# STM32F103RCT6.net
KiCad netlist of a schematic drawn in EasyEDA Pro
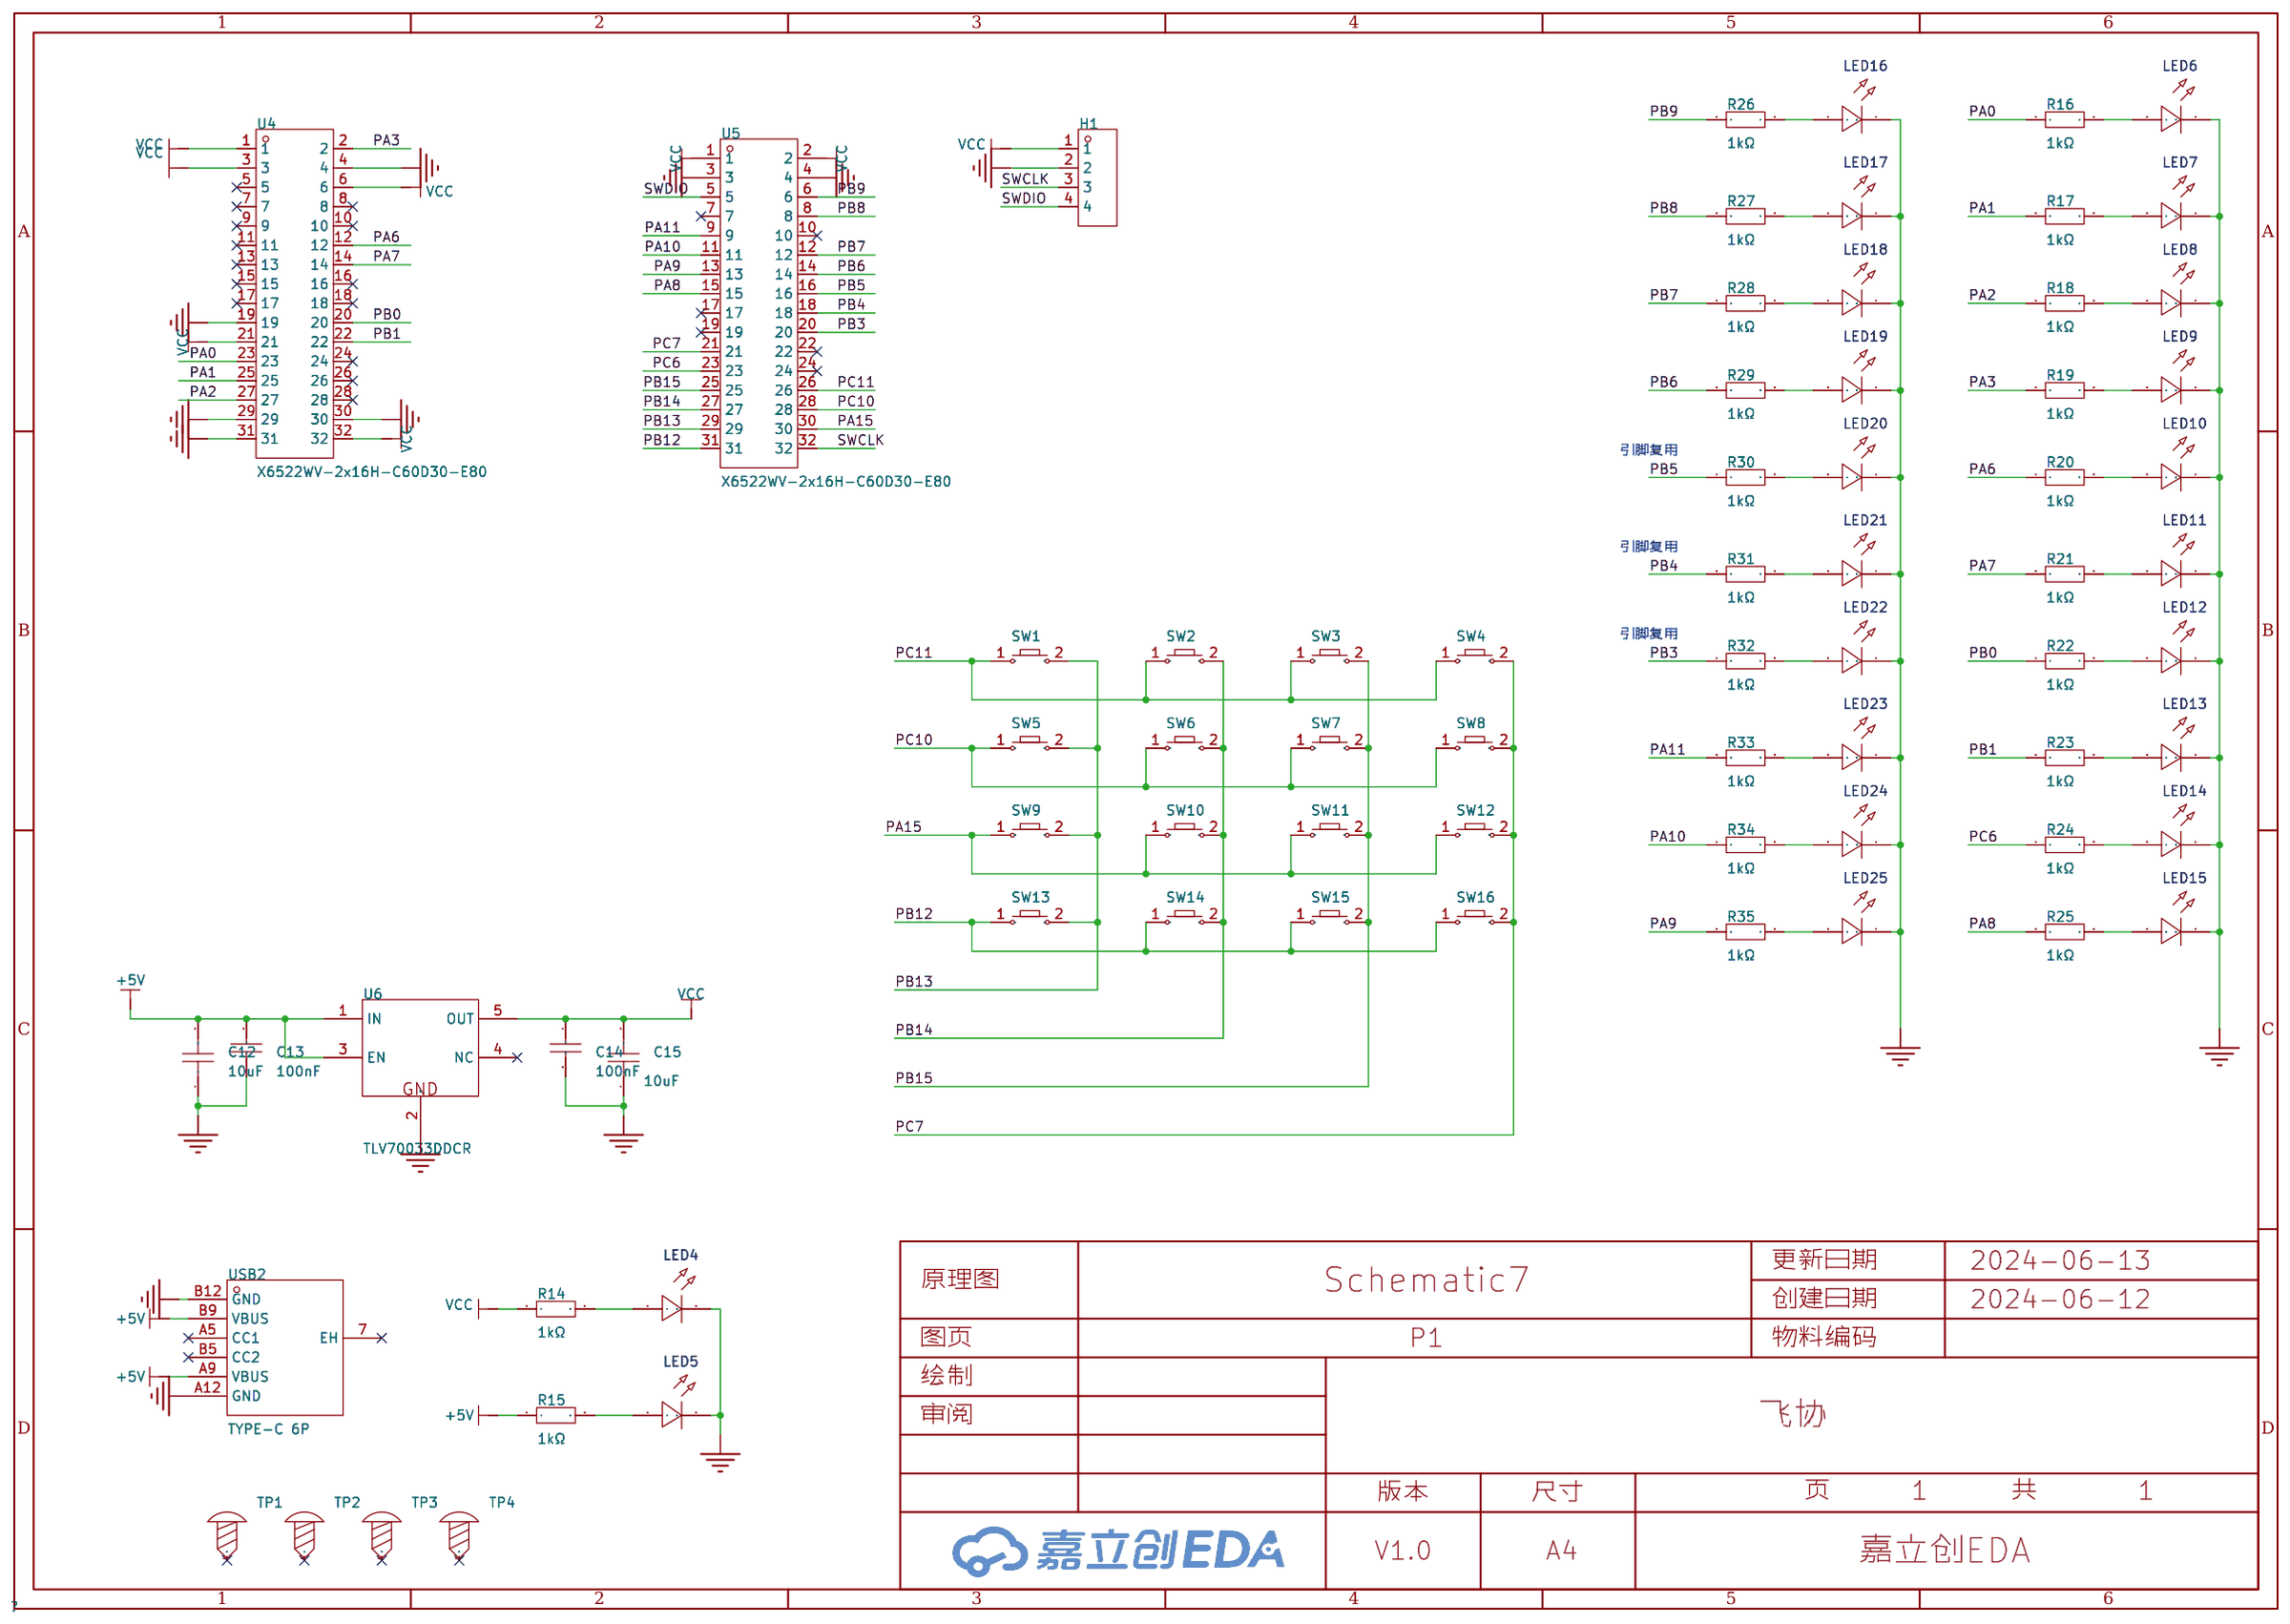
[diagram p0: schematic sheet]

(export (version "E")
  (design (tool "Eeschema 10.0.6"))
  (components
    (comp (ref "C12")
      (value "10uF")
      (fields
        (field (name "Manufacturer Part") "CL21A106KAYNNNE")
        (field (name "Manufacturer") "SAMSUNG(三星)")
      )
      (libsource (lib "easyedapro") (part "CL21A106KAYNNNE"))
    )
    (comp (ref "C13")
      (value "100nF")
      (footprint "easyedapro:C0805")
      (description "容值:100nF;精度:±10%;额定电压:50V;材质(温度系数):X7R;")
      (fields (field (name "Manufacturer Part") "0805B104K500NT") (field (name "Manufacturer") "FH(风华)"))
      (libsource (lib "easyedapro") (part "0805B104K500NT"))
    )
    (comp (ref "C14")
      (value "100nF")
      (footprint "easyedapro:C0805")
      (description "容值:100nF;精度:±10%;额定电压:50V;材质(温度系数):X7R;")
      (fields (field (name "Manufacturer Part") "0805B104K500NT") (field (name "Manufacturer") "FH(风华)"))
      (libsource (lib "easyedapro") (part "0805B104K500NT"))
    )
    (comp (ref "C15")
      (value "10uF")
      (fields
        (field (name "Manufacturer Part") "CL21A106KAYNNNE")
        (field (name "Manufacturer") "SAMSUNG(三星)")
      )
      (libsource (lib "easyedapro") (part "CL21A106KAYNNNE"))
    )
    (comp (ref "H1")
      (value "~")
      (footprint "easyedapro:HDR-TH_4P-P2.54-V-F")
      (libsource (lib "easyedapro") (part "2.54-1*4P母"))
    )
    (comp (ref "LED4")
      (value "~")
      (footprint "easyedapro:LED_0805")
      (libsource (lib "easyedapro") (part "LED_B"))
    )
    (comp (ref "LED5")
      (value "~")
      (footprint "easyedapro:LED_0805")
      (libsource (lib "easyedapro") (part "LED_B"))
    )
    (comp (ref "LED6")
      (value "~")
      (footprint "easyedapro:LED_0805")
      (libsource (lib "easyedapro") (part "LED_B"))
    )
    (comp (ref "LED7")
      (value "~")
      (footprint "easyedapro:LED_0805")
      (libsource (lib "easyedapro") (part "LED_B"))
    )
    (comp (ref "LED8")
      (value "~")
      (footprint "easyedapro:LED_0805")
      (libsource (lib "easyedapro") (part "LED_B"))
    )
    (comp (ref "LED9")
      (value "~")
      (footprint "easyedapro:LED_0805")
      (libsource (lib "easyedapro") (part "LED_B"))
    )
    (comp (ref "LED10")
      (value "~")
      (footprint "easyedapro:LED_0805")
      (libsource (lib "easyedapro") (part "LED_B"))
    )
    (comp (ref "LED11")
      (value "~")
      (footprint "easyedapro:LED_0805")
      (libsource (lib "easyedapro") (part "LED_B"))
    )
    (comp (ref "LED12")
      (value "~")
      (footprint "easyedapro:LED_0805")
      (libsource (lib "easyedapro") (part "LED_B"))
    )
    (comp (ref "LED13")
      (value "~")
      (footprint "easyedapro:LED_0805")
      (libsource (lib "easyedapro") (part "LED_B"))
    )
    (comp (ref "LED14")
      (value "~")
      (footprint "easyedapro:LED_0805")
      (libsource (lib "easyedapro") (part "LED_B"))
    )
    (comp (ref "LED15")
      (value "~")
      (footprint "easyedapro:LED_0805")
      (libsource (lib "easyedapro") (part "LED_B"))
    )
    (comp (ref "LED16")
      (value "~")
      (footprint "easyedapro:LED_0805")
      (libsource (lib "easyedapro") (part "LED_B"))
    )
    (comp (ref "LED17")
      (value "~")
      (footprint "easyedapro:LED_0805")
      (libsource (lib "easyedapro") (part "LED_B"))
    )
    (comp (ref "LED18")
      (value "~")
      (footprint "easyedapro:LED_0805")
      (libsource (lib "easyedapro") (part "LED_B"))
    )
    (comp (ref "LED19")
      (value "~")
      (footprint "easyedapro:LED_0805")
      (libsource (lib "easyedapro") (part "LED_B"))
    )
    (comp (ref "LED20")
      (value "~")
      (footprint "easyedapro:LED_0805")
      (libsource (lib "easyedapro") (part "LED_B"))
    )
    (comp (ref "LED21")
      (value "~")
      (footprint "easyedapro:LED_0805")
      (libsource (lib "easyedapro") (part "LED_B"))
    )
    (comp (ref "LED22")
      (value "~")
      (footprint "easyedapro:LED_0805")
      (libsource (lib "easyedapro") (part "LED_B"))
    )
    (comp (ref "LED23")
      (value "~")
      (footprint "easyedapro:LED_0805")
      (libsource (lib "easyedapro") (part "LED_B"))
    )
    (comp (ref "LED24")
      (value "~")
      (footprint "easyedapro:LED_0805")
      (libsource (lib "easyedapro") (part "LED_B"))
    )
    (comp (ref "LED25")
      (value "~")
      (footprint "easyedapro:LED_0805")
      (libsource (lib "easyedapro") (part "LED_B"))
    )
    (comp (ref "R14")
      (value "1kΩ")
      (footprint "easyedapro:R0805")
      (description "电阻类型:厚膜电阻;阻值:1kΩ;精度:±1%;功率:125mW;最大工作电压:150V;温度系数:±100ppm/°C;")
      (fields
        (field (name "Manufacturer Part") "0805W8F1001T5E")
        (field (name "Manufacturer") "UNI-ROYAL(厚声)")
      )
      (libsource (lib "easyedapro") (part "0805W8F1001T5E"))
    )
    (comp (ref "R15")
      (value "1kΩ")
      (footprint "easyedapro:R0805")
      (description "电阻类型:厚膜电阻;阻值:1kΩ;精度:±1%;功率:125mW;最大工作电压:150V;温度系数:±100ppm/°C;")
      (fields
        (field (name "Manufacturer Part") "0805W8F1001T5E")
        (field (name "Manufacturer") "UNI-ROYAL(厚声)")
      )
      (libsource (lib "easyedapro") (part "0805W8F1001T5E"))
    )
    (comp (ref "R16")
      (value "1kΩ")
      (footprint "easyedapro:R0805")
      (description "电阻类型:厚膜电阻;阻值:1kΩ;精度:±1%;功率:125mW;最大工作电压:150V;温度系数:±100ppm/°C;")
      (fields
        (field (name "Manufacturer Part") "0805W8F1001T5E")
        (field (name "Manufacturer") "UNI-ROYAL(厚声)")
      )
      (libsource (lib "easyedapro") (part "0805W8F1001T5E"))
    )
    (comp (ref "R17")
      (value "1kΩ")
      (footprint "easyedapro:R0805")
      (description "电阻类型:厚膜电阻;阻值:1kΩ;精度:±1%;功率:125mW;最大工作电压:150V;温度系数:±100ppm/°C;")
      (fields
        (field (name "Manufacturer Part") "0805W8F1001T5E")
        (field (name "Manufacturer") "UNI-ROYAL(厚声)")
      )
      (libsource (lib "easyedapro") (part "0805W8F1001T5E"))
    )
    (comp (ref "R18")
      (value "1kΩ")
      (footprint "easyedapro:R0805")
      (description "电阻类型:厚膜电阻;阻值:1kΩ;精度:±1%;功率:125mW;最大工作电压:150V;温度系数:±100ppm/°C;")
      (fields
        (field (name "Manufacturer Part") "0805W8F1001T5E")
        (field (name "Manufacturer") "UNI-ROYAL(厚声)")
      )
      (libsource (lib "easyedapro") (part "0805W8F1001T5E"))
    )
    (comp (ref "R19")
      (value "1kΩ")
      (footprint "easyedapro:R0805")
      (description "电阻类型:厚膜电阻;阻值:1kΩ;精度:±1%;功率:125mW;最大工作电压:150V;温度系数:±100ppm/°C;")
      (fields
        (field (name "Manufacturer Part") "0805W8F1001T5E")
        (field (name "Manufacturer") "UNI-ROYAL(厚声)")
      )
      (libsource (lib "easyedapro") (part "0805W8F1001T5E"))
    )
    (comp (ref "R20")
      (value "1kΩ")
      (footprint "easyedapro:R0805")
      (description "电阻类型:厚膜电阻;阻值:1kΩ;精度:±1%;功率:125mW;最大工作电压:150V;温度系数:±100ppm/°C;")
      (fields
        (field (name "Manufacturer Part") "0805W8F1001T5E")
        (field (name "Manufacturer") "UNI-ROYAL(厚声)")
      )
      (libsource (lib "easyedapro") (part "0805W8F1001T5E"))
    )
    (comp (ref "R21")
      (value "1kΩ")
      (footprint "easyedapro:R0805")
      (description "电阻类型:厚膜电阻;阻值:1kΩ;精度:±1%;功率:125mW;最大工作电压:150V;温度系数:±100ppm/°C;")
      (fields
        (field (name "Manufacturer Part") "0805W8F1001T5E")
        (field (name "Manufacturer") "UNI-ROYAL(厚声)")
      )
      (libsource (lib "easyedapro") (part "0805W8F1001T5E"))
    )
    (comp (ref "R22")
      (value "1kΩ")
      (footprint "easyedapro:R0805")
      (description "电阻类型:厚膜电阻;阻值:1kΩ;精度:±1%;功率:125mW;最大工作电压:150V;温度系数:±100ppm/°C;")
      (fields
        (field (name "Manufacturer Part") "0805W8F1001T5E")
        (field (name "Manufacturer") "UNI-ROYAL(厚声)")
      )
      (libsource (lib "easyedapro") (part "0805W8F1001T5E"))
    )
    (comp (ref "R23")
      (value "1kΩ")
      (footprint "easyedapro:R0805")
      (description "电阻类型:厚膜电阻;阻值:1kΩ;精度:±1%;功率:125mW;最大工作电压:150V;温度系数:±100ppm/°C;")
      (fields
        (field (name "Manufacturer Part") "0805W8F1001T5E")
        (field (name "Manufacturer") "UNI-ROYAL(厚声)")
      )
      (libsource (lib "easyedapro") (part "0805W8F1001T5E"))
    )
    (comp (ref "R24")
      (value "1kΩ")
      (footprint "easyedapro:R0805")
      (description "电阻类型:厚膜电阻;阻值:1kΩ;精度:±1%;功率:125mW;最大工作电压:150V;温度系数:±100ppm/°C;")
      (fields
        (field (name "Manufacturer Part") "0805W8F1001T5E")
        (field (name "Manufacturer") "UNI-ROYAL(厚声)")
      )
      (libsource (lib "easyedapro") (part "0805W8F1001T5E"))
    )
    (comp (ref "R25")
      (value "1kΩ")
      (footprint "easyedapro:R0805")
      (description "电阻类型:厚膜电阻;阻值:1kΩ;精度:±1%;功率:125mW;最大工作电压:150V;温度系数:±100ppm/°C;")
      (fields
        (field (name "Manufacturer Part") "0805W8F1001T5E")
        (field (name "Manufacturer") "UNI-ROYAL(厚声)")
      )
      (libsource (lib "easyedapro") (part "0805W8F1001T5E"))
    )
    (comp (ref "R26")
      (value "1kΩ")
      (footprint "easyedapro:R0805")
      (description "电阻类型:厚膜电阻;阻值:1kΩ;精度:±1%;功率:125mW;最大工作电压:150V;温度系数:±100ppm/°C;")
      (fields
        (field (name "Manufacturer Part") "0805W8F1001T5E")
        (field (name "Manufacturer") "UNI-ROYAL(厚声)")
      )
      (libsource (lib "easyedapro") (part "0805W8F1001T5E"))
    )
    (comp (ref "R27")
      (value "1kΩ")
      (footprint "easyedapro:R0805")
      (description "电阻类型:厚膜电阻;阻值:1kΩ;精度:±1%;功率:125mW;最大工作电压:150V;温度系数:±100ppm/°C;")
      (fields
        (field (name "Manufacturer Part") "0805W8F1001T5E")
        (field (name "Manufacturer") "UNI-ROYAL(厚声)")
      )
      (libsource (lib "easyedapro") (part "0805W8F1001T5E"))
    )
    (comp (ref "R28")
      (value "1kΩ")
      (footprint "easyedapro:R0805")
      (description "电阻类型:厚膜电阻;阻值:1kΩ;精度:±1%;功率:125mW;最大工作电压:150V;温度系数:±100ppm/°C;")
      (fields
        (field (name "Manufacturer Part") "0805W8F1001T5E")
        (field (name "Manufacturer") "UNI-ROYAL(厚声)")
      )
      (libsource (lib "easyedapro") (part "0805W8F1001T5E"))
    )
    (comp (ref "R29")
      (value "1kΩ")
      (footprint "easyedapro:R0805")
      (description "电阻类型:厚膜电阻;阻值:1kΩ;精度:±1%;功率:125mW;最大工作电压:150V;温度系数:±100ppm/°C;")
      (fields
        (field (name "Manufacturer Part") "0805W8F1001T5E")
        (field (name "Manufacturer") "UNI-ROYAL(厚声)")
      )
      (libsource (lib "easyedapro") (part "0805W8F1001T5E"))
    )
    (comp (ref "R30")
      (value "1kΩ")
      (footprint "easyedapro:R0805")
      (description "电阻类型:厚膜电阻;阻值:1kΩ;精度:±1%;功率:125mW;最大工作电压:150V;温度系数:±100ppm/°C;")
      (fields
        (field (name "Manufacturer Part") "0805W8F1001T5E")
        (field (name "Manufacturer") "UNI-ROYAL(厚声)")
      )
      (libsource (lib "easyedapro") (part "0805W8F1001T5E"))
    )
    (comp (ref "R31")
      (value "1kΩ")
      (footprint "easyedapro:R0805")
      (description "电阻类型:厚膜电阻;阻值:1kΩ;精度:±1%;功率:125mW;最大工作电压:150V;温度系数:±100ppm/°C;")
      (fields
        (field (name "Manufacturer Part") "0805W8F1001T5E")
        (field (name "Manufacturer") "UNI-ROYAL(厚声)")
      )
      (libsource (lib "easyedapro") (part "0805W8F1001T5E"))
    )
    (comp (ref "R32")
      (value "1kΩ")
      (footprint "easyedapro:R0805")
      (description "电阻类型:厚膜电阻;阻值:1kΩ;精度:±1%;功率:125mW;最大工作电压:150V;温度系数:±100ppm/°C;")
      (fields
        (field (name "Manufacturer Part") "0805W8F1001T5E")
        (field (name "Manufacturer") "UNI-ROYAL(厚声)")
      )
      (libsource (lib "easyedapro") (part "0805W8F1001T5E"))
    )
    (comp (ref "R33")
      (value "1kΩ")
      (footprint "easyedapro:R0805")
      (description "电阻类型:厚膜电阻;阻值:1kΩ;精度:±1%;功率:125mW;最大工作电压:150V;温度系数:±100ppm/°C;")
      (fields
        (field (name "Manufacturer Part") "0805W8F1001T5E")
        (field (name "Manufacturer") "UNI-ROYAL(厚声)")
      )
      (libsource (lib "easyedapro") (part "0805W8F1001T5E"))
    )
    (comp (ref "R34")
      (value "1kΩ")
      (footprint "easyedapro:R0805")
      (description "电阻类型:厚膜电阻;阻值:1kΩ;精度:±1%;功率:125mW;最大工作电压:150V;温度系数:±100ppm/°C;")
      (fields
        (field (name "Manufacturer Part") "0805W8F1001T5E")
        (field (name "Manufacturer") "UNI-ROYAL(厚声)")
      )
      (libsource (lib "easyedapro") (part "0805W8F1001T5E"))
    )
    (comp (ref "R35")
      (value "1kΩ")
      (footprint "easyedapro:R0805")
      (description "电阻类型:厚膜电阻;阻值:1kΩ;精度:±1%;功率:125mW;最大工作电压:150V;温度系数:±100ppm/°C;")
      (fields
        (field (name "Manufacturer Part") "0805W8F1001T5E")
        (field (name "Manufacturer") "UNI-ROYAL(厚声)")
      )
      (libsource (lib "easyedapro") (part "0805W8F1001T5E"))
    )
    (comp (ref "SW1")
      (value "~")
      (footprint "easyedapro:Key_SMD_3.6x6.1x2.5")
      (libsource (lib "easyedapro") (part "轻触按键x2"))
    )
    (comp (ref "SW2")
      (value "~")
      (footprint "easyedapro:Key_SMD_3.6x6.1x2.5")
      (libsource (lib "easyedapro") (part "轻触按键x2"))
    )
    (comp (ref "SW3")
      (value "~")
      (footprint "easyedapro:Key_SMD_3.6x6.1x2.5")
      (libsource (lib "easyedapro") (part "轻触按键x2"))
    )
    (comp (ref "SW4")
      (value "~")
      (footprint "easyedapro:Key_SMD_3.6x6.1x2.5")
      (libsource (lib "easyedapro") (part "轻触按键x2"))
    )
    (comp (ref "SW5")
      (value "~")
      (footprint "easyedapro:Key_SMD_3.6x6.1x2.5")
      (libsource (lib "easyedapro") (part "轻触按键x2"))
    )
    (comp (ref "SW6")
      (value "~")
      (footprint "easyedapro:Key_SMD_3.6x6.1x2.5")
      (libsource (lib "easyedapro") (part "轻触按键x2"))
    )
    (comp (ref "SW7")
      (value "~")
      (footprint "easyedapro:Key_SMD_3.6x6.1x2.5")
      (libsource (lib "easyedapro") (part "轻触按键x2"))
    )
    (comp (ref "SW8")
      (value "~")
      (footprint "easyedapro:Key_SMD_3.6x6.1x2.5")
      (libsource (lib "easyedapro") (part "轻触按键x2"))
    )
    (comp (ref "SW9")
      (value "~")
      (footprint "easyedapro:Key_SMD_3.6x6.1x2.5")
      (libsource (lib "easyedapro") (part "轻触按键x2"))
    )
    (comp (ref "SW10")
      (value "~")
      (footprint "easyedapro:Key_SMD_3.6x6.1x2.5")
      (libsource (lib "easyedapro") (part "轻触按键x2"))
    )
    (comp (ref "SW11")
      (value "~")
      (footprint "easyedapro:Key_SMD_3.6x6.1x2.5")
      (libsource (lib "easyedapro") (part "轻触按键x2"))
    )
    (comp (ref "SW12")
      (value "~")
      (footprint "easyedapro:Key_SMD_3.6x6.1x2.5")
      (libsource (lib "easyedapro") (part "轻触按键x2"))
    )
    (comp (ref "SW13")
      (value "~")
      (footprint "easyedapro:Key_SMD_3.6x6.1x2.5")
      (libsource (lib "easyedapro") (part "轻触按键x2"))
    )
    (comp (ref "SW14")
      (value "~")
      (footprint "easyedapro:Key_SMD_3.6x6.1x2.5")
      (libsource (lib "easyedapro") (part "轻触按键x2"))
    )
    (comp (ref "SW15")
      (value "~")
      (footprint "easyedapro:Key_SMD_3.6x6.1x2.5")
      (libsource (lib "easyedapro") (part "轻触按键x2"))
    )
    (comp (ref "SW16")
      (value "~")
      (footprint "easyedapro:Key_SMD_3.6x6.1x2.5")
      (libsource (lib "easyedapro") (part "轻触按键x2"))
    )
    (comp (ref "TP1") (value "~") (footprint "easyedapro:M3螺丝") (libsource (lib "easyedapro") (part "螺丝孔")))
    (comp (ref "TP2") (value "~") (footprint "easyedapro:M3螺丝") (libsource (lib "easyedapro") (part "螺丝孔")))
    (comp (ref "TP3") (value "~") (footprint "easyedapro:M3螺丝") (libsource (lib "easyedapro") (part "螺丝孔")))
    (comp (ref "TP4") (value "~") (footprint "easyedapro:M3螺丝") (libsource (lib "easyedapro") (part "螺丝孔")))
    (comp (ref "U4")
      (value "X6522WV-2x16H-C60D30-E80")
      (footprint "easyedapro:HDR-TH_32P-P2.54-V-M-R2-C16-S2.54-3")
      (fields (field (name "Manufacturer") "XKB Connection(中国星坤)"))
      (libsource (lib "easyedapro") (part "X6522WV-2X16H-C60D30-E80"))
    )
    (comp (ref "U5")
      (value "X6522WV-2x16H-C60D30-E80")
      (footprint "easyedapro:HDR-TH_32P-P2.54-V-M-R2-C16-S2.54-3")
      (fields (field (name "Manufacturer") "XKB Connection(中国星坤)"))
      (libsource (lib "easyedapro") (part "X6522WV-2X16H-C60D30-E80"))
    )
    (comp (ref "U6")
      (value "TLV70033DDCR")
      (footprint "easyedapro:SOT-23-5_L3.0-W1.7-P0.95-LS2.8-BR")
      (fields (field (name "Manufacturer") "TI(德州仪器)"))
      (libsource (lib "easyedapro") (part "TLV70033DDCR"))
    )
    (comp (ref "USB2")
      (value "TYPE-C 6P")
      (footprint "easyedapro:TYPE-C-SMD_TYPE-C-6P")
      (description "连接器类型:Type-C;标准:-;公母:母;端口数量:1;触点数量:6P;安装方式:卧贴;额定电流 - 电源:-;工作温度范围:-40°C~+85°C;")
      (fields (field (name "Manufacturer") "SHOU HAN(首韩)"))
      (libsource (lib "easyedapro") (part "TYPE-C 6P"))
    )
  )
  (nets
    (net (code "1") (name "+5V") (class "Default")
      (node (ref "C12") (pin "2") (pinfunction "2_2") (pintype "unspecified"))
      (node (ref "C13") (pin "2") (pinfunction "2_2") (pintype "input"))
      (node (ref "R15") (pin "1") (pinfunction "1_1") (pintype "input"))
      (node (ref "U6") (pin "1") (pinfunction "IN_1") (pintype "input"))
      (node (ref "U6") (pin "3") (pinfunction "EN_3") (pintype "input"))
      (node (ref "USB2") (pin "A9") (pinfunction "VBUS_A9") (pintype "unspecified"))
      (node (ref "USB2") (pin "B9") (pinfunction "VBUS_B9") (pintype "unspecified"))
    )
    (net (code "2") (name "/PA0") (class "Default")
      (node (ref "R16") (pin "1") (pinfunction "1_1") (pintype "input"))
      (node (ref "U4") (pin "23") (pinfunction "23_23") (pintype "unspecified"))
    )
    (net (code "3") (name "/PA1") (class "Default")
      (node (ref "R17") (pin "1") (pinfunction "1_1") (pintype "input"))
      (node (ref "U4") (pin "25") (pinfunction "25_25") (pintype "unspecified"))
    )
    (net (code "4") (name "/PA2") (class "Default")
      (node (ref "R18") (pin "1") (pinfunction "1_1") (pintype "input"))
      (node (ref "U4") (pin "27") (pinfunction "27_27") (pintype "unspecified"))
    )
    (net (code "5") (name "/PA3") (class "Default")
      (node (ref "R19") (pin "1") (pinfunction "1_1") (pintype "input"))
      (node (ref "U4") (pin "2") (pinfunction "2_2") (pintype "unspecified"))
    )
    (net (code "6") (name "/PA6") (class "Default")
      (node (ref "R20") (pin "1") (pinfunction "1_1") (pintype "input"))
      (node (ref "U4") (pin "12") (pinfunction "12_12") (pintype "unspecified"))
    )
    (net (code "7") (name "/PA7") (class "Default")
      (node (ref "R21") (pin "1") (pinfunction "1_1") (pintype "input"))
      (node (ref "U4") (pin "14") (pinfunction "14_14") (pintype "unspecified"))
    )
    (net (code "8") (name "/PA8") (class "Default")
      (node (ref "R25") (pin "1") (pinfunction "1_1") (pintype "input"))
      (node (ref "U5") (pin "15") (pinfunction "15_15") (pintype "unspecified"))
    )
    (net (code "9") (name "/PA9") (class "Default")
      (node (ref "R35") (pin "1") (pinfunction "1_1") (pintype "input"))
      (node (ref "U5") (pin "13") (pinfunction "13_13") (pintype "unspecified"))
    )
    (net (code "10") (name "/PA10") (class "Default")
      (node (ref "R34") (pin "1") (pinfunction "1_1") (pintype "input"))
      (node (ref "U5") (pin "11") (pinfunction "11_11") (pintype "unspecified"))
    )
    (net (code "11") (name "/PA11") (class "Default")
      (node (ref "R33") (pin "1") (pinfunction "1_1") (pintype "input"))
      (node (ref "U5") (pin "9") (pinfunction "9_9") (pintype "unspecified"))
    )
    (net (code "12") (name "/PA15") (class "Default")
      (node (ref "SW10") (pin "1") (pinfunction "1_1") (pintype "input"))
      (node (ref "SW11") (pin "1") (pinfunction "1_1") (pintype "input"))
      (node (ref "SW12") (pin "1") (pinfunction "1_1") (pintype "input"))
      (node (ref "SW9") (pin "1") (pinfunction "1_1") (pintype "input"))
      (node (ref "U5") (pin "30") (pinfunction "30_30") (pintype "unspecified"))
    )
    (net (code "13") (name "/PB0") (class "Default")
      (node (ref "R22") (pin "1") (pinfunction "1_1") (pintype "input"))
      (node (ref "U4") (pin "20") (pinfunction "20_20") (pintype "unspecified"))
    )
    (net (code "14") (name "/PB1") (class "Default")
      (node (ref "R23") (pin "1") (pinfunction "1_1") (pintype "input"))
      (node (ref "U4") (pin "22") (pinfunction "22_22") (pintype "unspecified"))
    )
    (net (code "15") (name "/PB3") (class "Default")
      (node (ref "R32") (pin "1") (pinfunction "1_1") (pintype "input"))
      (node (ref "U5") (pin "20") (pinfunction "20_20") (pintype "unspecified"))
    )
    (net (code "16") (name "/PB4") (class "Default")
      (node (ref "R31") (pin "1") (pinfunction "1_1") (pintype "input"))
      (node (ref "U5") (pin "18") (pinfunction "18_18") (pintype "unspecified"))
    )
    (net (code "17") (name "/PB5") (class "Default")
      (node (ref "R30") (pin "1") (pinfunction "1_1") (pintype "input"))
      (node (ref "U5") (pin "16") (pinfunction "16_16") (pintype "unspecified"))
    )
    (net (code "18") (name "/PB6") (class "Default")
      (node (ref "R29") (pin "1") (pinfunction "1_1") (pintype "input"))
      (node (ref "U5") (pin "14") (pinfunction "14_14") (pintype "unspecified"))
    )
    (net (code "19") (name "/PB7") (class "Default")
      (node (ref "R28") (pin "1") (pinfunction "1_1") (pintype "input"))
      (node (ref "U5") (pin "12") (pinfunction "12_12") (pintype "unspecified"))
    )
    (net (code "20") (name "/PB8") (class "Default")
      (node (ref "R27") (pin "1") (pinfunction "1_1") (pintype "input"))
      (node (ref "U5") (pin "8") (pinfunction "8_8") (pintype "unspecified"))
    )
    (net (code "21") (name "/PB9") (class "Default")
      (node (ref "R26") (pin "1") (pinfunction "1_1") (pintype "input"))
      (node (ref "U5") (pin "6") (pinfunction "6_6") (pintype "unspecified"))
    )
    (net (code "22") (name "/PB12") (class "Default")
      (node (ref "SW13") (pin "1") (pinfunction "1_1") (pintype "input"))
      (node (ref "SW14") (pin "1") (pinfunction "1_1") (pintype "input"))
      (node (ref "SW15") (pin "1") (pinfunction "1_1") (pintype "input"))
      (node (ref "SW16") (pin "1") (pinfunction "1_1") (pintype "input"))
      (node (ref "U5") (pin "31") (pinfunction "31_31") (pintype "unspecified"))
    )
    (net (code "23") (name "/PB13") (class "Default")
      (node (ref "SW1") (pin "2") (pinfunction "2_2") (pintype "input"))
      (node (ref "SW13") (pin "2") (pinfunction "2_2") (pintype "input"))
      (node (ref "SW5") (pin "2") (pinfunction "2_2") (pintype "input"))
      (node (ref "SW9") (pin "2") (pinfunction "2_2") (pintype "input"))
      (node (ref "U5") (pin "29") (pinfunction "29_29") (pintype "unspecified"))
    )
    (net (code "24") (name "/PB14") (class "Default")
      (node (ref "SW10") (pin "2") (pinfunction "2_2") (pintype "input"))
      (node (ref "SW14") (pin "2") (pinfunction "2_2") (pintype "input"))
      (node (ref "SW2") (pin "2") (pinfunction "2_2") (pintype "input"))
      (node (ref "SW6") (pin "2") (pinfunction "2_2") (pintype "input"))
      (node (ref "U5") (pin "27") (pinfunction "27_27") (pintype "unspecified"))
    )
    (net (code "25") (name "/PB15") (class "Default")
      (node (ref "SW11") (pin "2") (pinfunction "2_2") (pintype "input"))
      (node (ref "SW15") (pin "2") (pinfunction "2_2") (pintype "input"))
      (node (ref "SW3") (pin "2") (pinfunction "2_2") (pintype "input"))
      (node (ref "SW7") (pin "2") (pinfunction "2_2") (pintype "input"))
      (node (ref "U5") (pin "25") (pinfunction "25_25") (pintype "unspecified"))
    )
    (net (code "26") (name "/PC6") (class "Default")
      (node (ref "R24") (pin "1") (pinfunction "1_1") (pintype "input"))
      (node (ref "U5") (pin "23") (pinfunction "23_23") (pintype "unspecified"))
    )
    (net (code "27") (name "/PC7") (class "Default")
      (node (ref "SW12") (pin "2") (pinfunction "2_2") (pintype "input"))
      (node (ref "SW16") (pin "2") (pinfunction "2_2") (pintype "input"))
      (node (ref "SW4") (pin "2") (pinfunction "2_2") (pintype "input"))
      (node (ref "SW8") (pin "2") (pinfunction "2_2") (pintype "input"))
      (node (ref "U5") (pin "21") (pinfunction "21_21") (pintype "unspecified"))
    )
    (net (code "28") (name "/PC10") (class "Default")
      (node (ref "SW5") (pin "1") (pinfunction "1_1") (pintype "input"))
      (node (ref "SW6") (pin "1") (pinfunction "1_1") (pintype "input"))
      (node (ref "SW7") (pin "1") (pinfunction "1_1") (pintype "input"))
      (node (ref "SW8") (pin "1") (pinfunction "1_1") (pintype "input"))
      (node (ref "U5") (pin "28") (pinfunction "28_28") (pintype "unspecified"))
    )
    (net (code "29") (name "/PC11") (class "Default")
      (node (ref "SW1") (pin "1") (pinfunction "1_1") (pintype "input"))
      (node (ref "SW2") (pin "1") (pinfunction "1_1") (pintype "input"))
      (node (ref "SW3") (pin "1") (pinfunction "1_1") (pintype "input"))
      (node (ref "SW4") (pin "1") (pinfunction "1_1") (pintype "input"))
      (node (ref "U5") (pin "26") (pinfunction "26_26") (pintype "unspecified"))
    )
    (net (code "30") (name "/SWCLK") (class "Default")
      (node (ref "H1") (pin "3") (pinfunction "3_3") (pintype "unspecified"))
      (node (ref "U5") (pin "32") (pinfunction "32_32") (pintype "unspecified"))
    )
    (net (code "31") (name "/SWDIO") (class "Default")
      (node (ref "H1") (pin "4") (pinfunction "4_4") (pintype "unspecified"))
      (node (ref "U5") (pin "5") (pinfunction "5_5") (pintype "unspecified"))
    )
    (net (code "32") (name "GND") (class "Default")
      (node (ref "C12") (pin "1") (pinfunction "1_1") (pintype "unspecified"))
      (node (ref "C13") (pin "1") (pinfunction "1_1") (pintype "input"))
      (node (ref "C14") (pin "2") (pinfunction "2_2") (pintype "input"))
      (node (ref "C15") (pin "1") (pinfunction "1_1") (pintype "unspecified"))
      (node (ref "H1") (pin "2") (pinfunction "2_2") (pintype "unspecified"))
      (node (ref "LED10") (pin "1") (pinfunction "C_1") (pintype "input"))
      (node (ref "LED11") (pin "1") (pinfunction "C_1") (pintype "input"))
      (node (ref "LED12") (pin "1") (pinfunction "C_1") (pintype "input"))
      (node (ref "LED13") (pin "1") (pinfunction "C_1") (pintype "input"))
      (node (ref "LED14") (pin "1") (pinfunction "C_1") (pintype "input"))
      (node (ref "LED15") (pin "1") (pinfunction "C_1") (pintype "input"))
      (node (ref "LED16") (pin "1") (pinfunction "C_1") (pintype "input"))
      (node (ref "LED17") (pin "1") (pinfunction "C_1") (pintype "input"))
      (node (ref "LED18") (pin "1") (pinfunction "C_1") (pintype "input"))
      (node (ref "LED19") (pin "1") (pinfunction "C_1") (pintype "input"))
      (node (ref "LED20") (pin "1") (pinfunction "C_1") (pintype "input"))
      (node (ref "LED21") (pin "1") (pinfunction "C_1") (pintype "input"))
      (node (ref "LED22") (pin "1") (pinfunction "C_1") (pintype "input"))
      (node (ref "LED23") (pin "1") (pinfunction "C_1") (pintype "input"))
      (node (ref "LED24") (pin "1") (pinfunction "C_1") (pintype "input"))
      (node (ref "LED25") (pin "1") (pinfunction "C_1") (pintype "input"))
      (node (ref "LED4") (pin "1") (pinfunction "C_1") (pintype "input"))
      (node (ref "LED5") (pin "1") (pinfunction "C_1") (pintype "input"))
      (node (ref "LED6") (pin "1") (pinfunction "C_1") (pintype "input"))
      (node (ref "LED7") (pin "1") (pinfunction "C_1") (pintype "input"))
      (node (ref "LED8") (pin "1") (pinfunction "C_1") (pintype "input"))
      (node (ref "LED9") (pin "1") (pinfunction "C_1") (pintype "input"))
      (node (ref "U4") (pin "19") (pinfunction "19_19") (pintype "unspecified"))
      (node (ref "U4") (pin "29") (pinfunction "29_29") (pintype "unspecified"))
      (node (ref "U4") (pin "30") (pinfunction "30_30") (pintype "unspecified"))
      (node (ref "U4") (pin "31") (pinfunction "31_31") (pintype "unspecified"))
      (node (ref "U4") (pin "4") (pinfunction "4_4") (pintype "unspecified"))
      (node (ref "U5") (pin "3") (pinfunction "3_3") (pintype "unspecified"))
      (node (ref "U5") (pin "4") (pinfunction "4_4") (pintype "unspecified"))
      (node (ref "U6") (pin "2") (pinfunction "GND_2") (pintype "input"))
      (node (ref "USB2") (pin "A12") (pinfunction "GND_A12") (pintype "unspecified"))
      (node (ref "USB2") (pin "B12") (pinfunction "GND_B12") (pintype "unspecified"))
    )
    (net (code "33") (name "Net-(LED4-A)") (class "Default")
      (node (ref "LED4") (pin "2") (pinfunction "A_2") (pintype "input"))
      (node (ref "R14") (pin "2") (pinfunction "2_2") (pintype "input"))
    )
    (net (code "34") (name "Net-(LED5-A)") (class "Default")
      (node (ref "LED5") (pin "2") (pinfunction "A_2") (pintype "input"))
      (node (ref "R15") (pin "2") (pinfunction "2_2") (pintype "input"))
    )
    (net (code "35") (name "Net-(LED6-A)") (class "Default")
      (node (ref "LED6") (pin "2") (pinfunction "A_2") (pintype "input"))
      (node (ref "R16") (pin "2") (pinfunction "2_2") (pintype "input"))
    )
    (net (code "36") (name "Net-(LED7-A)") (class "Default")
      (node (ref "LED7") (pin "2") (pinfunction "A_2") (pintype "input"))
      (node (ref "R17") (pin "2") (pinfunction "2_2") (pintype "input"))
    )
    (net (code "37") (name "Net-(LED8-A)") (class "Default")
      (node (ref "LED8") (pin "2") (pinfunction "A_2") (pintype "input"))
      (node (ref "R18") (pin "2") (pinfunction "2_2") (pintype "input"))
    )
    (net (code "38") (name "Net-(LED9-A)") (class "Default")
      (node (ref "LED9") (pin "2") (pinfunction "A_2") (pintype "input"))
      (node (ref "R19") (pin "2") (pinfunction "2_2") (pintype "input"))
    )
    (net (code "39") (name "Net-(LED10-A)") (class "Default")
      (node (ref "LED10") (pin "2") (pinfunction "A_2") (pintype "input"))
      (node (ref "R20") (pin "2") (pinfunction "2_2") (pintype "input"))
    )
    (net (code "40") (name "Net-(LED11-A)") (class "Default")
      (node (ref "LED11") (pin "2") (pinfunction "A_2") (pintype "input"))
      (node (ref "R21") (pin "2") (pinfunction "2_2") (pintype "input"))
    )
    (net (code "41") (name "Net-(LED12-A)") (class "Default")
      (node (ref "LED12") (pin "2") (pinfunction "A_2") (pintype "input"))
      (node (ref "R22") (pin "2") (pinfunction "2_2") (pintype "input"))
    )
    (net (code "42") (name "Net-(LED13-A)") (class "Default")
      (node (ref "LED13") (pin "2") (pinfunction "A_2") (pintype "input"))
      (node (ref "R23") (pin "2") (pinfunction "2_2") (pintype "input"))
    )
    (net (code "43") (name "Net-(LED14-A)") (class "Default")
      (node (ref "LED14") (pin "2") (pinfunction "A_2") (pintype "input"))
      (node (ref "R24") (pin "2") (pinfunction "2_2") (pintype "input"))
    )
    (net (code "44") (name "Net-(LED15-A)") (class "Default")
      (node (ref "LED15") (pin "2") (pinfunction "A_2") (pintype "input"))
      (node (ref "R25") (pin "2") (pinfunction "2_2") (pintype "input"))
    )
    (net (code "45") (name "Net-(LED16-A)") (class "Default")
      (node (ref "LED16") (pin "2") (pinfunction "A_2") (pintype "input"))
      (node (ref "R26") (pin "2") (pinfunction "2_2") (pintype "input"))
    )
    (net (code "46") (name "Net-(LED17-A)") (class "Default")
      (node (ref "LED17") (pin "2") (pinfunction "A_2") (pintype "input"))
      (node (ref "R27") (pin "2") (pinfunction "2_2") (pintype "input"))
    )
    (net (code "47") (name "Net-(LED18-A)") (class "Default")
      (node (ref "LED18") (pin "2") (pinfunction "A_2") (pintype "input"))
      (node (ref "R28") (pin "2") (pinfunction "2_2") (pintype "input"))
    )
    (net (code "48") (name "Net-(LED19-A)") (class "Default")
      (node (ref "LED19") (pin "2") (pinfunction "A_2") (pintype "input"))
      (node (ref "R29") (pin "2") (pinfunction "2_2") (pintype "input"))
    )
    (net (code "49") (name "Net-(LED20-A)") (class "Default")
      (node (ref "LED20") (pin "2") (pinfunction "A_2") (pintype "input"))
      (node (ref "R30") (pin "2") (pinfunction "2_2") (pintype "input"))
    )
    (net (code "50") (name "Net-(LED21-A)") (class "Default")
      (node (ref "LED21") (pin "2") (pinfunction "A_2") (pintype "input"))
      (node (ref "R31") (pin "2") (pinfunction "2_2") (pintype "input"))
    )
    (net (code "51") (name "Net-(LED22-A)") (class "Default")
      (node (ref "LED22") (pin "2") (pinfunction "A_2") (pintype "input"))
      (node (ref "R32") (pin "2") (pinfunction "2_2") (pintype "input"))
    )
    (net (code "52") (name "Net-(LED23-A)") (class "Default")
      (node (ref "LED23") (pin "2") (pinfunction "A_2") (pintype "input"))
      (node (ref "R33") (pin "2") (pinfunction "2_2") (pintype "input"))
    )
    (net (code "53") (name "Net-(LED24-A)") (class "Default")
      (node (ref "LED24") (pin "2") (pinfunction "A_2") (pintype "input"))
      (node (ref "R34") (pin "2") (pinfunction "2_2") (pintype "input"))
    )
    (net (code "54") (name "Net-(LED25-A)") (class "Default")
      (node (ref "LED25") (pin "2") (pinfunction "A_2") (pintype "input"))
      (node (ref "R35") (pin "2") (pinfunction "2_2") (pintype "input"))
    )
    (net (code "55") (name "VCC") (class "Default")
      (node (ref "C14") (pin "1") (pinfunction "1_1") (pintype "input"))
      (node (ref "C15") (pin "2") (pinfunction "2_2") (pintype "unspecified"))
      (node (ref "H1") (pin "1") (pinfunction "1_1") (pintype "unspecified"))
      (node (ref "R14") (pin "1") (pinfunction "1_1") (pintype "input"))
      (node (ref "U4") (pin "1") (pinfunction "1_1") (pintype "unspecified"))
      (node (ref "U4") (pin "21") (pinfunction "21_21") (pintype "unspecified"))
      (node (ref "U4") (pin "3") (pinfunction "3_3") (pintype "unspecified"))
      (node (ref "U4") (pin "32") (pinfunction "32_32") (pintype "unspecified"))
      (node (ref "U4") (pin "6") (pinfunction "6_6") (pintype "unspecified"))
      (node (ref "U5") (pin "1") (pinfunction "1_1") (pintype "unspecified"))
      (node (ref "U5") (pin "2") (pinfunction "2_2") (pintype "unspecified"))
      (node (ref "U6") (pin "5") (pinfunction "OUT_5") (pintype "input"))
    )
    (net (code "56") (name "unconnected-(TP1-Pad1)") (class "Default")
      (node (ref "TP1") (pin "1") (pinfunction "1_1") (pintype "input+no_connect"))
    )
    (net (code "57") (name "unconnected-(TP2-Pad1)") (class "Default")
      (node (ref "TP2") (pin "1") (pinfunction "1_1") (pintype "input+no_connect"))
    )
    (net (code "58") (name "unconnected-(TP3-Pad1)") (class "Default")
      (node (ref "TP3") (pin "1") (pinfunction "1_1") (pintype "input+no_connect"))
    )
    (net (code "59") (name "unconnected-(TP4-Pad1)") (class "Default")
      (node (ref "TP4") (pin "1") (pinfunction "1_1") (pintype "input+no_connect"))
    )
    (net (code "60") (name "unconnected-(U4-Pad5)") (class "Default")
      (node (ref "U4") (pin "5") (pinfunction "5_5") (pintype "unspecified+no_connect"))
    )
    (net (code "61") (name "unconnected-(U4-Pad7)") (class "Default")
      (node (ref "U4") (pin "7") (pinfunction "7_7") (pintype "unspecified+no_connect"))
    )
    (net (code "62") (name "unconnected-(U4-Pad8)") (class "Default")
      (node (ref "U4") (pin "8") (pinfunction "8_8") (pintype "unspecified+no_connect"))
    )
    (net (code "63") (name "unconnected-(U4-Pad9)") (class "Default")
      (node (ref "U4") (pin "9") (pinfunction "9_9") (pintype "unspecified+no_connect"))
    )
    (net (code "64") (name "unconnected-(U4-Pad10)") (class "Default")
      (node (ref "U4") (pin "10") (pinfunction "10_10") (pintype "unspecified+no_connect"))
    )
    (net (code "65") (name "unconnected-(U4-Pad11)") (class "Default")
      (node (ref "U4") (pin "11") (pinfunction "11_11") (pintype "unspecified+no_connect"))
    )
    (net (code "66") (name "unconnected-(U4-Pad13)") (class "Default")
      (node (ref "U4") (pin "13") (pinfunction "13_13") (pintype "unspecified+no_connect"))
    )
    (net (code "67") (name "unconnected-(U4-Pad15)") (class "Default")
      (node (ref "U4") (pin "15") (pinfunction "15_15") (pintype "unspecified+no_connect"))
    )
    (net (code "68") (name "unconnected-(U4-Pad16)") (class "Default")
      (node (ref "U4") (pin "16") (pinfunction "16_16") (pintype "unspecified+no_connect"))
    )
    (net (code "69") (name "unconnected-(U4-Pad17)") (class "Default")
      (node (ref "U4") (pin "17") (pinfunction "17_17") (pintype "unspecified+no_connect"))
    )
    (net (code "70") (name "unconnected-(U4-Pad18)") (class "Default")
      (node (ref "U4") (pin "18") (pinfunction "18_18") (pintype "unspecified+no_connect"))
    )
    (net (code "71") (name "unconnected-(U4-Pad24)") (class "Default")
      (node (ref "U4") (pin "24") (pinfunction "24_24") (pintype "unspecified+no_connect"))
    )
    (net (code "72") (name "unconnected-(U4-Pad26)") (class "Default")
      (node (ref "U4") (pin "26") (pinfunction "26_26") (pintype "unspecified+no_connect"))
    )
    (net (code "73") (name "unconnected-(U4-Pad28)") (class "Default")
      (node (ref "U4") (pin "28") (pinfunction "28_28") (pintype "unspecified+no_connect"))
    )
    (net (code "74") (name "unconnected-(U5-Pad7)") (class "Default")
      (node (ref "U5") (pin "7") (pinfunction "7_7") (pintype "unspecified+no_connect"))
    )
    (net (code "75") (name "unconnected-(U5-Pad10)") (class "Default")
      (node (ref "U5") (pin "10") (pinfunction "10_10") (pintype "unspecified+no_connect"))
    )
    (net (code "76") (name "unconnected-(U5-Pad17)") (class "Default")
      (node (ref "U5") (pin "17") (pinfunction "17_17") (pintype "unspecified+no_connect"))
    )
    (net (code "77") (name "unconnected-(U5-Pad19)") (class "Default")
      (node (ref "U5") (pin "19") (pinfunction "19_19") (pintype "unspecified+no_connect"))
    )
    (net (code "78") (name "unconnected-(U5-Pad22)") (class "Default")
      (node (ref "U5") (pin "22") (pinfunction "22_22") (pintype "unspecified+no_connect"))
    )
    (net (code "79") (name "unconnected-(U5-Pad24)") (class "Default")
      (node (ref "U5") (pin "24") (pinfunction "24_24") (pintype "unspecified+no_connect"))
    )
    (net (code "80") (name "unconnected-(U6-NC-Pad4)") (class "Default")
      (node (ref "U6") (pin "4") (pinfunction "NC_4") (pintype "input+no_connect"))
    )
    (net (code "81") (name "unconnected-(USB2-CC1-PadA5)") (class "Default")
      (node (ref "USB2") (pin "A5") (pinfunction "CC1_A5") (pintype "unspecified+no_connect"))
    )
    (net (code "82") (name "unconnected-(USB2-CC2-PadB5)") (class "Default")
      (node (ref "USB2") (pin "B5") (pinfunction "CC2_B5") (pintype "unspecified+no_connect"))
    )
    (net (code "83") (name "unconnected-(USB2-EH-Pad7)") (class "Default")
      (node (ref "USB2") (pin "7") (pinfunction "EH_7") (pintype "unspecified+no_connect"))
    )
  )
)
